# Apple1.net
KiCad netlist of a schematic drawn in EAGLE
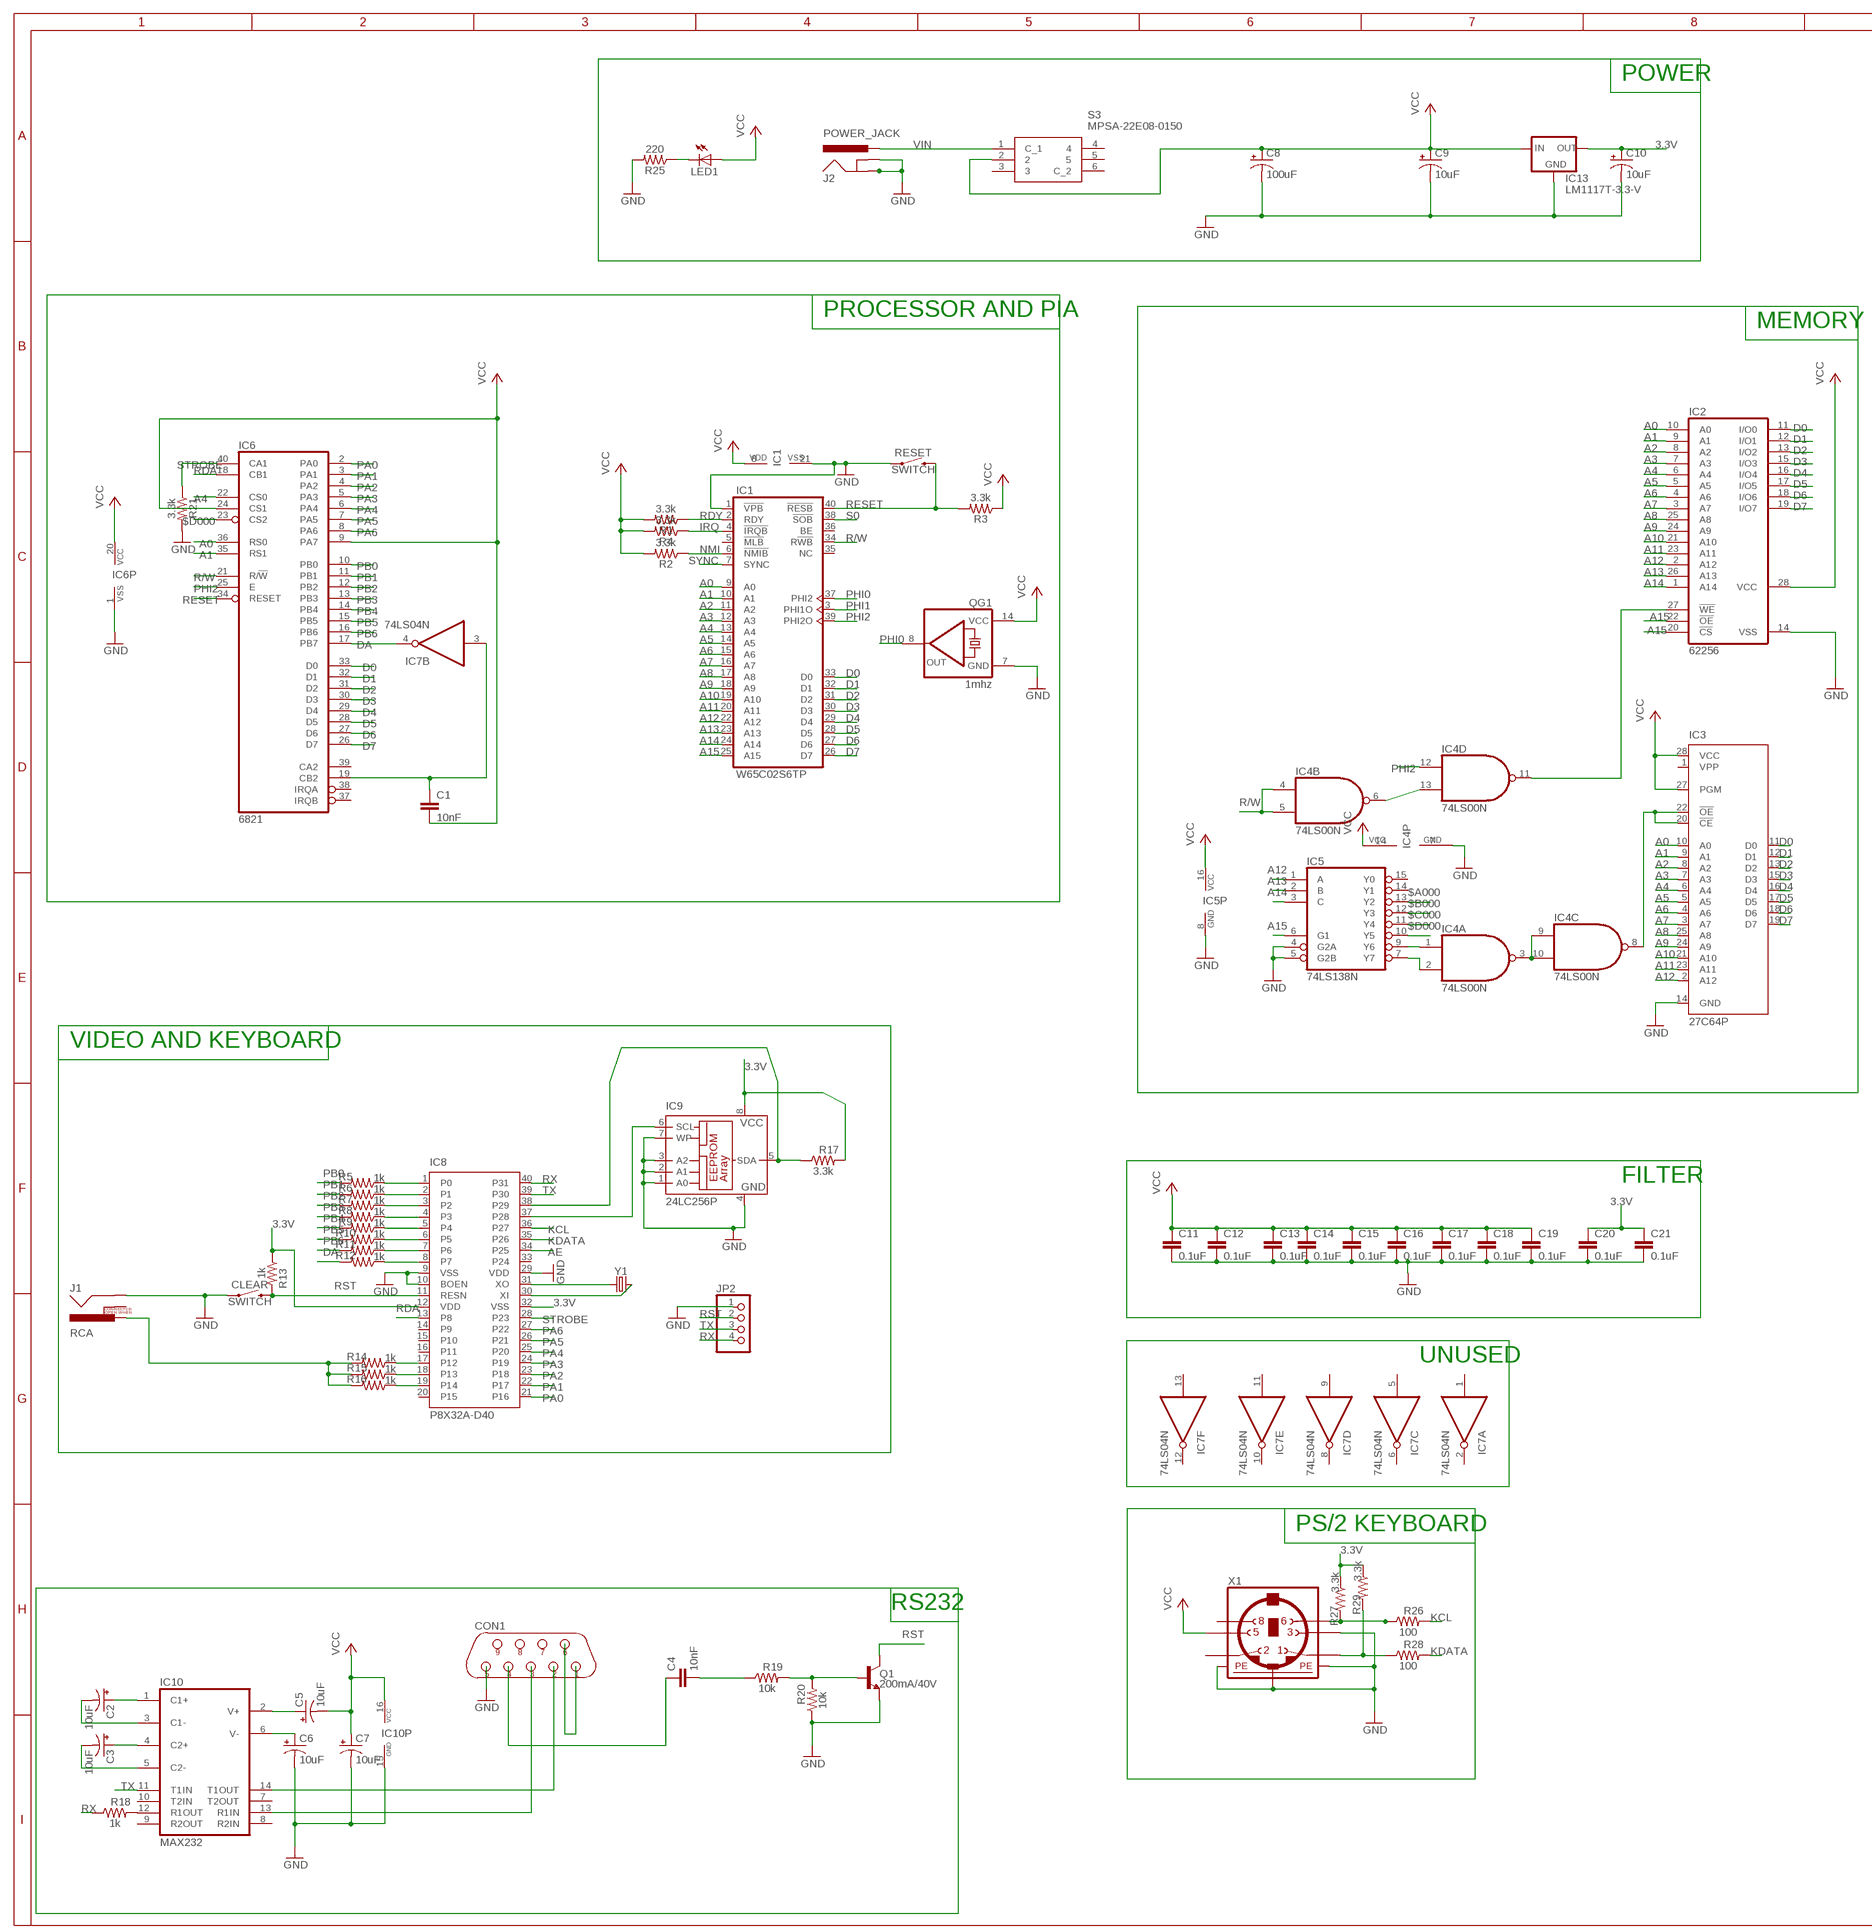
[diagram p0: schematic, sheet 1, part 1 of 2]
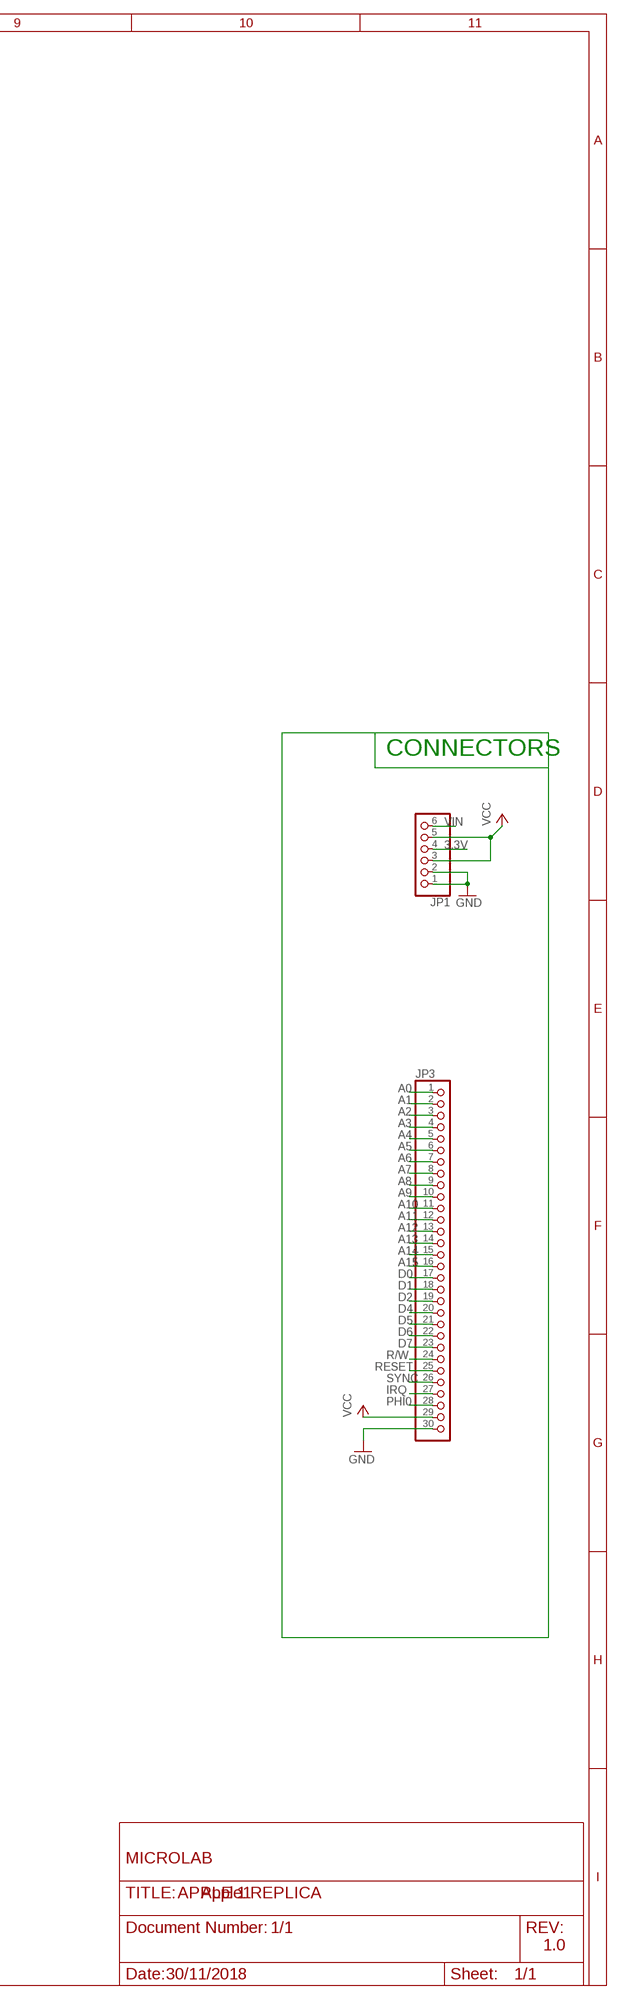
[diagram p1: schematic, sheet 1, part 2 of 2]

(export (version "E")
  (design (tool "Eeschema 10.0.6"))
  (components
    (comp (ref "C1")
      (value "10nF")
      (footprint "eagle-import:CAP-PTH-10MM")
      (libsource (lib "eagle-import") (part "10NF-PTH-10MM-10000V-1-%"))
    )
    (comp (ref "C2")
      (value "10uF")
      (footprint "eagle-import:CPOL-RADIAL-2.5MM-5MM")
      (libsource (lib "eagle-import") (part "10UF-POLAR-RADIAL-2.5MM-25V-20%"))
    )
    (comp (ref "C3")
      (value "10uF")
      (footprint "eagle-import:CPOL-RADIAL-2.5MM-5MM")
      (libsource (lib "eagle-import") (part "10UF-POLAR-RADIAL-2.5MM-25V-20%"))
    )
    (comp (ref "C4")
      (value "10nF")
      (footprint "eagle-import:CAP-PTH-10MM")
      (libsource (lib "eagle-import") (part "10NF-PTH-10MM-10000V-1-%"))
    )
    (comp (ref "C5")
      (value "10uF")
      (footprint "eagle-import:CPOL-RADIAL-2.5MM-5MM")
      (libsource (lib "eagle-import") (part "10UF-POLAR-RADIAL-2.5MM-25V-20%"))
    )
    (comp (ref "C6")
      (value "10uF")
      (footprint "eagle-import:CPOL-RADIAL-2.5MM-5MM")
      (libsource (lib "eagle-import") (part "10UF-POLAR-RADIAL-2.5MM-25V-20%"))
    )
    (comp (ref "C7")
      (value "10uF")
      (footprint "eagle-import:CPOL-RADIAL-2.5MM-5MM")
      (libsource (lib "eagle-import") (part "10UF-POLAR-RADIAL-2.5MM-25V-20%"))
    )
    (comp (ref "C8")
      (value "100uF")
      (footprint "eagle-import:CPOL-RADIAL-2.5MM-6.5MM")
      (libsource (lib "eagle-import") (part "100UF-POLAR-RADIAL-2.5MM-25V-20%"))
    )
    (comp (ref "C9")
      (value "10uF")
      (footprint "eagle-import:CPOL-RADIAL-2.5MM-5MM")
      (libsource (lib "eagle-import") (part "10UF-POLAR-RADIAL-2.5MM-25V-20%"))
    )
    (comp (ref "C10")
      (value "10uF")
      (footprint "eagle-import:CPOL-RADIAL-2.5MM-5MM")
      (libsource (lib "eagle-import") (part "10UF-POLAR-RADIAL-2.5MM-25V-20%"))
    )
    (comp (ref "C11")
      (value "0.1uF")
      (footprint "eagle-import:CAP-PTH-SMALL-KIT")
      (libsource (lib "eagle-import") (part "0.1UF-KIT-EZ-50V-20%"))
    )
    (comp (ref "C12")
      (value "0.1uF")
      (footprint "eagle-import:CAP-PTH-SMALL-KIT")
      (libsource (lib "eagle-import") (part "0.1UF-KIT-EZ-50V-20%"))
    )
    (comp (ref "C13")
      (value "0.1uF")
      (footprint "eagle-import:CAP-PTH-SMALL-KIT")
      (libsource (lib "eagle-import") (part "0.1UF-KIT-EZ-50V-20%"))
    )
    (comp (ref "C14")
      (value "0.1uF")
      (footprint "eagle-import:CAP-PTH-SMALL-KIT")
      (libsource (lib "eagle-import") (part "0.1UF-KIT-EZ-50V-20%"))
    )
    (comp (ref "C15")
      (value "0.1uF")
      (footprint "eagle-import:CAP-PTH-SMALL-KIT")
      (libsource (lib "eagle-import") (part "0.1UF-KIT-EZ-50V-20%"))
    )
    (comp (ref "C16")
      (value "0.1uF")
      (footprint "eagle-import:CAP-PTH-SMALL-KIT")
      (libsource (lib "eagle-import") (part "0.1UF-KIT-EZ-50V-20%"))
    )
    (comp (ref "C17")
      (value "0.1uF")
      (footprint "eagle-import:CAP-PTH-SMALL-KIT")
      (libsource (lib "eagle-import") (part "0.1UF-KIT-EZ-50V-20%"))
    )
    (comp (ref "C18")
      (value "0.1uF")
      (footprint "eagle-import:CAP-PTH-SMALL-KIT")
      (libsource (lib "eagle-import") (part "0.1UF-KIT-EZ-50V-20%"))
    )
    (comp (ref "C19")
      (value "0.1uF")
      (footprint "eagle-import:CAP-PTH-SMALL-KIT")
      (libsource (lib "eagle-import") (part "0.1UF-KIT-EZ-50V-20%"))
    )
    (comp (ref "C20")
      (value "0.1uF")
      (footprint "eagle-import:CAP-PTH-SMALL-KIT")
      (libsource (lib "eagle-import") (part "0.1UF-KIT-EZ-50V-20%"))
    )
    (comp (ref "C21")
      (value "0.1uF")
      (footprint "eagle-import:CAP-PTH-SMALL-KIT")
      (libsource (lib "eagle-import") (part "0.1UF-KIT-EZ-50V-20%"))
    )
    (comp (ref "CLEAR")
      (value "SWITCH")
      (footprint "eagle-import:TACTILE_SWITCH_PTH_6.0MM")
      (libsource (lib "eagle-import") (part "MOMENTARY-SWITCH-SPST-PTH-6.0MM"))
    )
    (comp (ref "CON1")
      (value "DB9F")
      (footprint "eagle-import:D-09F")
      (libsource (lib "eagle-import") (part "DB9F"))
    )
    (comp (ref "IC1")
      (value "W65C02S6TP")
      (footprint "eagle-import:DIL40")
      (libsource (lib "eagle-import") (part "W65C02SP6T"))
    )
    (comp (ref "IC2")
      (value "62256")
      (footprint "eagle-import:DIL28-6")
      (libsource (lib "eagle-import") (part "62256P"))
    )
    (comp (ref "IC3")
      (value "27C64P")
      (footprint "eagle-import:DIL28-6")
      (fields (field (name "MF") "Arrow Electronics") (field (name "MPN") "M27C64A-10F1"))
      (libsource (lib "eagle-import") (part "2764PC"))
    )
    (comp (ref "IC4")
      (value "74LS00N")
      (footprint "eagle-import:DIL14")
      (libsource (lib "eagle-import") (part "7400NLS"))
    )
    (comp (ref "IC5")
      (value "74LS138N")
      (footprint "eagle-import:DIL16")
      (libsource (lib "eagle-import") (part "74138NLS"))
    )
    (comp (ref "IC6")
      (value "6821")
      (footprint "eagle-import:DIL40")
      (fields (field (name "MF") "NTE ELECTRONICS") (field (name "MPN") "NTE6821"))
      (libsource (lib "eagle-import") (part "6821"))
    )
    (comp (ref "IC7")
      (value "74LS04N")
      (footprint "eagle-import:DIL14")
      (libsource (lib "eagle-import") (part "7404NLS"))
    )
    (comp (ref "IC8")
      (value "P8X32A-D40")
      (footprint "eagle-import:DIL40")
      (fields (field (name "MF") "Parallax Semiconductor"))
      (libsource (lib "eagle-import") (part "P8X32A-D40"))
    )
    (comp (ref "IC9")
      (value "24LC256P")
      (footprint "eagle-import:DIL8")
      (fields (field (name "MF") "MICROCHIP") (field (name "MPN") "24LC256-E/P"))
      (libsource (lib "eagle-import") (part "24PLC256"))
    )
    (comp (ref "IC10")
      (value "MAX232")
      (footprint "eagle-import:DIL16")
      (fields (field (name "MF") "MAXIM") (field (name "MPN") "MAX232ACPE+"))
      (libsource (lib "eagle-import") (part "MAX232"))
    )
    (comp (ref "IC13")
      (value "LM1117T-3.3-V")
      (footprint "eagle-import:TO220V")
      (libsource (lib "eagle-import") (part "LM1117T--V3.3"))
    )
    (comp (ref "J1")
      (value "RCA")
      (footprint "eagle-import:RCA")
      (libsource (lib "eagle-import") (part "RCA"))
    )
    (comp (ref "J2")
      (value "POWER_JACK")
      (footprint "eagle-import:POWER_JACK_PTH")
      (libsource (lib "eagle-import") (part "POWER_JACK"))
    )
    (comp (ref "JP1")
      (value "PINHD-1X6B")
      (footprint "eagle-import:1X06-BIG")
      (libsource (lib "eagle-import") (part "PINHD-1X6B"))
    )
    (comp (ref "JP2")
      (value "PINHD-1X4")
      (footprint "eagle-import:1X04")
      (libsource (lib "eagle-import") (part "PINHD-1X4"))
    )
    (comp (ref "JP3")
      (value "PINHD-1X30")
      (footprint "eagle-import:1X30")
      (libsource (lib "eagle-import") (part "PINHD-1X30"))
    )
    (comp (ref "LED1")
      (value "LED5MM")
      (footprint "eagle-import:LED5MM")
      (libsource (lib "eagle-import") (part "LED5MM"))
    )
    (comp (ref "Q1")
      (value "200mA/40V")
      (footprint "eagle-import:TO-92")
      (libsource (lib "eagle-import") (part "TRANS_NPN-2N3904"))
    )
    (comp (ref "QG1")
      (value "1mhz")
      (footprint "eagle-import:DIL14S")
      (libsource (lib "eagle-import") (part "QG5860"))
    )
    (comp (ref "R1")
      (value "3.3k")
      (footprint "eagle-import:AXIAL-0.3")
      (libsource (lib "eagle-import") (part "10KOHM-HORIZ-1/4W-5%"))
    )
    (comp (ref "R2")
      (value "3.3k")
      (footprint "eagle-import:AXIAL-0.3")
      (libsource (lib "eagle-import") (part "10KOHM-HORIZ-1/4W-5%"))
    )
    (comp (ref "R3")
      (value "3.3k")
      (footprint "eagle-import:AXIAL-0.3")
      (libsource (lib "eagle-import") (part "10KOHM-HORIZ-1/4W-5%"))
    )
    (comp (ref "R4")
      (value "3.3k")
      (footprint "eagle-import:AXIAL-0.3")
      (libsource (lib "eagle-import") (part "10KOHM-HORIZ-1/4W-5%"))
    )
    (comp (ref "R5")
      (value "1k")
      (footprint "eagle-import:AXIAL-0.3")
      (libsource (lib "eagle-import") (part "10KOHM-HORIZ-1/4W-5%"))
    )
    (comp (ref "R6")
      (value "1k")
      (footprint "eagle-import:AXIAL-0.3")
      (libsource (lib "eagle-import") (part "10KOHM-HORIZ-1/4W-5%"))
    )
    (comp (ref "R7")
      (value "1k")
      (footprint "eagle-import:AXIAL-0.3")
      (libsource (lib "eagle-import") (part "10KOHM-HORIZ-1/4W-5%"))
    )
    (comp (ref "R8")
      (value "1k")
      (footprint "eagle-import:AXIAL-0.3")
      (libsource (lib "eagle-import") (part "10KOHM-HORIZ-1/4W-5%"))
    )
    (comp (ref "R9")
      (value "1k")
      (footprint "eagle-import:AXIAL-0.3")
      (libsource (lib "eagle-import") (part "10KOHM-HORIZ-1/4W-5%"))
    )
    (comp (ref "R10")
      (value "1k")
      (footprint "eagle-import:AXIAL-0.3")
      (libsource (lib "eagle-import") (part "10KOHM-HORIZ-1/4W-5%"))
    )
    (comp (ref "R11")
      (value "1k")
      (footprint "eagle-import:AXIAL-0.3")
      (libsource (lib "eagle-import") (part "10KOHM-HORIZ-1/4W-5%"))
    )
    (comp (ref "R12")
      (value "1k")
      (footprint "eagle-import:AXIAL-0.3")
      (libsource (lib "eagle-import") (part "10KOHM-HORIZ-1/4W-5%"))
    )
    (comp (ref "R13")
      (value "1k")
      (footprint "eagle-import:AXIAL-0.3")
      (libsource (lib "eagle-import") (part "10KOHM-HORIZ-1/4W-5%"))
    )
    (comp (ref "R14")
      (value "1k")
      (footprint "eagle-import:AXIAL-0.3")
      (libsource (lib "eagle-import") (part "10KOHM-HORIZ-1/4W-5%"))
    )
    (comp (ref "R15")
      (value "1k")
      (footprint "eagle-import:AXIAL-0.3")
      (libsource (lib "eagle-import") (part "10KOHM-HORIZ-1/4W-5%"))
    )
    (comp (ref "R16")
      (value "1k")
      (footprint "eagle-import:AXIAL-0.3")
      (libsource (lib "eagle-import") (part "10KOHM-HORIZ-1/4W-5%"))
    )
    (comp (ref "R17")
      (value "3.3k")
      (footprint "eagle-import:AXIAL-0.3")
      (libsource (lib "eagle-import") (part "10KOHM-HORIZ-1/4W-5%"))
    )
    (comp (ref "R18")
      (value "1k")
      (footprint "eagle-import:AXIAL-0.3")
      (libsource (lib "eagle-import") (part "10KOHM-HORIZ-1/4W-5%"))
    )
    (comp (ref "R19")
      (value "10k")
      (footprint "eagle-import:AXIAL-0.3")
      (libsource (lib "eagle-import") (part "10KOHM-HORIZ-1/4W-5%"))
    )
    (comp (ref "R20")
      (value "10k")
      (footprint "eagle-import:AXIAL-0.3")
      (libsource (lib "eagle-import") (part "10KOHM-HORIZ-1/4W-5%"))
    )
    (comp (ref "R21")
      (value "3.3k")
      (footprint "eagle-import:AXIAL-0.3")
      (libsource (lib "eagle-import") (part "10KOHM-HORIZ-1/4W-5%"))
    )
    (comp (ref "R25")
      (value "220")
      (footprint "eagle-import:AXIAL-0.3")
      (libsource (lib "eagle-import") (part "10KOHM-HORIZ-1/4W-5%"))
    )
    (comp (ref "R26")
      (value "100")
      (footprint "eagle-import:AXIAL-0.3")
      (libsource (lib "eagle-import") (part "10KOHM-HORIZ-1/4W-5%"))
    )
    (comp (ref "R27")
      (value "3.3k")
      (footprint "eagle-import:AXIAL-0.3")
      (libsource (lib "eagle-import") (part "10KOHM-HORIZ-1/4W-5%"))
    )
    (comp (ref "R28")
      (value "100")
      (footprint "eagle-import:AXIAL-0.3")
      (libsource (lib "eagle-import") (part "10KOHM-HORIZ-1/4W-5%"))
    )
    (comp (ref "R29")
      (value "3.3k")
      (footprint "eagle-import:AXIAL-0.3")
      (libsource (lib "eagle-import") (part "10KOHM-HORIZ-1/4W-5%"))
    )
    (comp (ref "RESET")
      (value "SWITCH")
      (footprint "eagle-import:TACTILE_SWITCH_PTH_6.0MM")
      (libsource (lib "eagle-import") (part "MOMENTARY-SWITCH-SPST-PTH-6.0MM"))
    )
    (comp (ref "S3")
      (value "MPSA-22E08-0150")
      (footprint "eagle-import:MPSA22E080150")
      (fields (field (name "RS_PART_NUMBER") "9138895"))
      (libsource (lib "eagle-import") (part "MPSA-22E08-0150"))
    )
    (comp (ref "X1")
      (value "MINI_DIN_6")
      (footprint "eagle-import:M_DIN6")
      (libsource (lib "eagle-import") (part "MINI_DIN_6"))
    )
    (comp (ref "Y1")
      (value "CRYSTALPTH-HC49UV")
      (footprint "eagle-import:HC49U")
      (libsource (lib "eagle-import") (part "CRYSTALPTH-HC49UV"))
    )
  )
  (nets
    (net (code "1") (name "/$A000") (class "Default")
      (node (ref "IC5") (pin "13") (pinfunction "Y2_13") (pintype "output"))
    )
    (net (code "2") (name "/$B000") (class "Default")
      (node (ref "IC5") (pin "12") (pinfunction "Y3_12") (pintype "output"))
    )
    (net (code "3") (name "/$C000") (class "Default")
      (node (ref "IC5") (pin "11") (pinfunction "Y4_11") (pintype "output"))
    )
    (net (code "4") (name "/$D000") (class "Default")
      (node (ref "IC5") (pin "10") (pinfunction "Y5_10") (pintype "output"))
      (node (ref "IC6") (pin "23") (pinfunction "CS2_23") (pintype "input"))
    )
    (net (code "5") (name "/3.3V") (class "Default")
      (node (ref "C10") (pin "1") (pinfunction "+_1") (pintype "passive"))
      (node (ref "C20") (pin "1") (pinfunction "1_1") (pintype "passive"))
      (node (ref "C21") (pin "1") (pinfunction "1_1") (pintype "passive"))
      (node (ref "IC13") (pin "2") (pinfunction "OUT_2") (pintype "passive"))
      (node (ref "IC8") (pin "12") (pinfunction "VDD_12") (pintype "power_in"))
      (node (ref "IC8") (pin "32") (pinfunction "VSS_32") (pintype "power_in"))
      (node (ref "IC9") (pin "8") (pinfunction "VCC_8") (pintype "power_in"))
      (node (ref "JP1") (pin "4") (pinfunction "4_4") (pintype "passive"))
      (node (ref "R13") (pin "P$1") (pinfunction "1_P$1") (pintype "passive"))
      (node (ref "R17") (pin "P$2") (pinfunction "2_P$2") (pintype "passive"))
      (node (ref "R27") (pin "P$1") (pinfunction "1_P$1") (pintype "passive"))
      (node (ref "R29") (pin "P$1") (pinfunction "1_P$1") (pintype "passive"))
    )
    (net (code "6") (name "/A0") (class "Default")
      (node (ref "IC1") (pin "9") (pinfunction "A0_9") (pintype "output"))
      (node (ref "IC2") (pin "10") (pinfunction "A0_10") (pintype "input"))
      (node (ref "IC3") (pin "10") (pinfunction "A0_10") (pintype "input"))
      (node (ref "IC6") (pin "36") (pinfunction "RS0_36") (pintype "input"))
      (node (ref "JP3") (pin "1") (pinfunction "1_1") (pintype "passive"))
    )
    (net (code "7") (name "/A1") (class "Default")
      (node (ref "IC1") (pin "10") (pinfunction "A1_10") (pintype "output"))
      (node (ref "IC2") (pin "9") (pinfunction "A1_9") (pintype "input"))
      (node (ref "IC3") (pin "9") (pinfunction "A1_9") (pintype "input"))
      (node (ref "IC6") (pin "35") (pinfunction "RS1_35") (pintype "input"))
      (node (ref "JP3") (pin "2") (pinfunction "2_2") (pintype "passive"))
    )
    (net (code "8") (name "/A2") (class "Default")
      (node (ref "IC1") (pin "11") (pinfunction "A2_11") (pintype "output"))
      (node (ref "IC2") (pin "8") (pinfunction "A2_8") (pintype "input"))
      (node (ref "IC3") (pin "8") (pinfunction "A2_8") (pintype "input"))
      (node (ref "JP3") (pin "3") (pinfunction "3_3") (pintype "passive"))
    )
    (net (code "9") (name "/A3") (class "Default")
      (node (ref "IC1") (pin "12") (pinfunction "A3_12") (pintype "output"))
      (node (ref "IC2") (pin "7") (pinfunction "A3_7") (pintype "input"))
      (node (ref "IC3") (pin "7") (pinfunction "A3_7") (pintype "input"))
      (node (ref "JP3") (pin "4") (pinfunction "4_4") (pintype "passive"))
    )
    (net (code "10") (name "/A4") (class "Default")
      (node (ref "IC1") (pin "13") (pinfunction "A4_13") (pintype "output"))
      (node (ref "IC2") (pin "6") (pinfunction "A4_6") (pintype "input"))
      (node (ref "IC3") (pin "6") (pinfunction "A4_6") (pintype "input"))
      (node (ref "IC6") (pin "22") (pinfunction "CS0_22") (pintype "input"))
      (node (ref "JP3") (pin "5") (pinfunction "5_5") (pintype "passive"))
    )
    (net (code "11") (name "/A5") (class "Default")
      (node (ref "IC1") (pin "14") (pinfunction "A5_14") (pintype "output"))
      (node (ref "IC2") (pin "5") (pinfunction "A5_5") (pintype "input"))
      (node (ref "IC3") (pin "5") (pinfunction "A5_5") (pintype "input"))
      (node (ref "JP3") (pin "6") (pinfunction "6_6") (pintype "passive"))
    )
    (net (code "12") (name "/A6") (class "Default")
      (node (ref "IC1") (pin "15") (pinfunction "A6_15") (pintype "output"))
      (node (ref "IC2") (pin "4") (pinfunction "A6_4") (pintype "input"))
      (node (ref "IC3") (pin "4") (pinfunction "A6_4") (pintype "input"))
      (node (ref "JP3") (pin "7") (pinfunction "7_7") (pintype "passive"))
    )
    (net (code "13") (name "/A7") (class "Default")
      (node (ref "IC1") (pin "16") (pinfunction "A7_16") (pintype "output"))
      (node (ref "IC2") (pin "3") (pinfunction "A7_3") (pintype "input"))
      (node (ref "IC3") (pin "3") (pinfunction "A7_3") (pintype "input"))
      (node (ref "JP3") (pin "8") (pinfunction "8_8") (pintype "passive"))
    )
    (net (code "14") (name "/A8") (class "Default")
      (node (ref "IC1") (pin "17") (pinfunction "A8_17") (pintype "output"))
      (node (ref "IC2") (pin "25") (pinfunction "A8_25") (pintype "input"))
      (node (ref "IC3") (pin "25") (pinfunction "A8_25") (pintype "input"))
      (node (ref "JP3") (pin "9") (pinfunction "9_9") (pintype "passive"))
    )
    (net (code "15") (name "/A9") (class "Default")
      (node (ref "IC1") (pin "18") (pinfunction "A9_18") (pintype "output"))
      (node (ref "IC2") (pin "24") (pinfunction "A9_24") (pintype "input"))
      (node (ref "IC3") (pin "24") (pinfunction "A9_24") (pintype "input"))
      (node (ref "JP3") (pin "10") (pinfunction "10_10") (pintype "passive"))
    )
    (net (code "16") (name "/A10") (class "Default")
      (node (ref "IC1") (pin "19") (pinfunction "A10_19") (pintype "output"))
      (node (ref "IC2") (pin "21") (pinfunction "A10_21") (pintype "input"))
      (node (ref "IC3") (pin "21") (pinfunction "A10_21") (pintype "input"))
      (node (ref "JP3") (pin "11") (pinfunction "11_11") (pintype "passive"))
    )
    (net (code "17") (name "/A11") (class "Default")
      (node (ref "IC1") (pin "20") (pinfunction "A11_20") (pintype "output"))
      (node (ref "IC2") (pin "23") (pinfunction "A11_23") (pintype "input"))
      (node (ref "IC3") (pin "23") (pinfunction "A11_23") (pintype "input"))
      (node (ref "JP3") (pin "12") (pinfunction "12_12") (pintype "passive"))
    )
    (net (code "18") (name "/A12") (class "Default")
      (node (ref "IC1") (pin "22") (pinfunction "A12_22") (pintype "output"))
      (node (ref "IC2") (pin "2") (pinfunction "A12_2") (pintype "input"))
      (node (ref "IC3") (pin "2") (pinfunction "A12_2") (pintype "input"))
      (node (ref "IC5") (pin "1") (pinfunction "A_1") (pintype "input"))
      (node (ref "JP3") (pin "13") (pinfunction "13_13") (pintype "passive"))
    )
    (net (code "19") (name "/A13") (class "Default")
      (node (ref "IC1") (pin "23") (pinfunction "A13_23") (pintype "output"))
      (node (ref "IC2") (pin "26") (pinfunction "A13_26") (pintype "input"))
      (node (ref "IC5") (pin "2") (pinfunction "B_2") (pintype "input"))
      (node (ref "JP3") (pin "14") (pinfunction "14_14") (pintype "passive"))
    )
    (net (code "20") (name "/A14") (class "Default")
      (node (ref "IC1") (pin "24") (pinfunction "A14_24") (pintype "output"))
      (node (ref "IC2") (pin "1") (pinfunction "A14_1") (pintype "input"))
      (node (ref "IC5") (pin "3") (pinfunction "C_3") (pintype "input"))
      (node (ref "JP3") (pin "15") (pinfunction "15_15") (pintype "passive"))
    )
    (net (code "21") (name "/A15") (class "Default")
      (node (ref "IC1") (pin "25") (pinfunction "A15_25") (pintype "output"))
      (node (ref "IC2") (pin "20") (pinfunction "~{CS}_20") (pintype "input"))
      (node (ref "IC2") (pin "22") (pinfunction "~{OE}_22") (pintype "input"))
      (node (ref "IC5") (pin "6") (pinfunction "G1_6") (pintype "input"))
      (node (ref "JP3") (pin "16") (pinfunction "16_16") (pintype "passive"))
    )
    (net (code "22") (name "/AE") (class "Default")
      (node (ref "IC8") (pin "34") (pinfunction "P25_34") (pintype "bidirectional"))
    )
    (net (code "23") (name "/D0") (class "Default")
      (node (ref "IC1") (pin "33") (pinfunction "D0_33") (pintype "bidirectional"))
      (node (ref "IC2") (pin "11") (pinfunction "I/O0_11") (pintype "bidirectional"))
      (node (ref "IC3") (pin "11") (pinfunction "D0_11") (pintype "tri_state"))
      (node (ref "IC6") (pin "33") (pinfunction "D0_33") (pintype "bidirectional"))
      (node (ref "JP3") (pin "17") (pinfunction "17_17") (pintype "passive"))
    )
    (net (code "24") (name "/D1") (class "Default")
      (node (ref "IC1") (pin "32") (pinfunction "D1_32") (pintype "bidirectional"))
      (node (ref "IC2") (pin "12") (pinfunction "I/O1_12") (pintype "bidirectional"))
      (node (ref "IC3") (pin "12") (pinfunction "D1_12") (pintype "tri_state"))
      (node (ref "IC6") (pin "32") (pinfunction "D1_32") (pintype "bidirectional"))
      (node (ref "JP3") (pin "18") (pinfunction "18_18") (pintype "passive"))
    )
    (net (code "25") (name "/D2") (class "Default")
      (node (ref "IC1") (pin "31") (pinfunction "D2_31") (pintype "bidirectional"))
      (node (ref "IC2") (pin "13") (pinfunction "I/O2_13") (pintype "bidirectional"))
      (node (ref "IC3") (pin "13") (pinfunction "D2_13") (pintype "tri_state"))
      (node (ref "IC6") (pin "31") (pinfunction "D2_31") (pintype "bidirectional"))
      (node (ref "JP3") (pin "19") (pinfunction "19_19") (pintype "passive"))
    )
    (net (code "26") (name "/D3") (class "Default")
      (node (ref "IC1") (pin "30") (pinfunction "D3_30") (pintype "bidirectional"))
      (node (ref "IC2") (pin "15") (pinfunction "I/O3_15") (pintype "bidirectional"))
      (node (ref "IC3") (pin "15") (pinfunction "D3_15") (pintype "tri_state"))
      (node (ref "IC6") (pin "30") (pinfunction "D3_30") (pintype "bidirectional"))
    )
    (net (code "27") (name "/D4") (class "Default")
      (node (ref "IC1") (pin "29") (pinfunction "D4_29") (pintype "bidirectional"))
      (node (ref "IC2") (pin "16") (pinfunction "I/O4_16") (pintype "bidirectional"))
      (node (ref "IC3") (pin "16") (pinfunction "D4_16") (pintype "tri_state"))
      (node (ref "IC6") (pin "29") (pinfunction "D4_29") (pintype "bidirectional"))
      (node (ref "JP3") (pin "20") (pinfunction "20_20") (pintype "passive"))
    )
    (net (code "28") (name "/D5") (class "Default")
      (node (ref "IC1") (pin "28") (pinfunction "D5_28") (pintype "bidirectional"))
      (node (ref "IC2") (pin "17") (pinfunction "I/O5_17") (pintype "bidirectional"))
      (node (ref "IC3") (pin "17") (pinfunction "D5_17") (pintype "tri_state"))
      (node (ref "IC6") (pin "28") (pinfunction "D5_28") (pintype "bidirectional"))
      (node (ref "JP3") (pin "21") (pinfunction "21_21") (pintype "passive"))
    )
    (net (code "29") (name "/D6") (class "Default")
      (node (ref "IC1") (pin "27") (pinfunction "D6_27") (pintype "bidirectional"))
      (node (ref "IC2") (pin "18") (pinfunction "I/O6_18") (pintype "bidirectional"))
      (node (ref "IC3") (pin "18") (pinfunction "D6_18") (pintype "tri_state"))
      (node (ref "IC6") (pin "27") (pinfunction "D6_27") (pintype "bidirectional"))
      (node (ref "JP3") (pin "22") (pinfunction "22_22") (pintype "passive"))
    )
    (net (code "30") (name "/D7") (class "Default")
      (node (ref "IC1") (pin "26") (pinfunction "D7_26") (pintype "bidirectional"))
      (node (ref "IC2") (pin "19") (pinfunction "I/O7_19") (pintype "bidirectional"))
      (node (ref "IC3") (pin "19") (pinfunction "D7_19") (pintype "tri_state"))
      (node (ref "IC6") (pin "26") (pinfunction "D7_26") (pintype "bidirectional"))
      (node (ref "JP3") (pin "23") (pinfunction "23_23") (pintype "passive"))
    )
    (net (code "31") (name "/DA") (class "Default")
      (node (ref "IC6") (pin "17") (pinfunction "PB7_17") (pintype "bidirectional"))
      (node (ref "IC7") (pin "4") (pinfunction "O_4") (pintype "output"))
      (node (ref "R12") (pin "P$2") (pinfunction "2_P$2") (pintype "passive"))
    )
    (net (code "32") (name "/IRQ") (class "Default")
      (node (ref "IC1") (pin "4") (pinfunction "~{IRQB}_4") (pintype "input"))
      (node (ref "JP3") (pin "27") (pinfunction "27_27") (pintype "passive"))
      (node (ref "R4") (pin "P$1") (pinfunction "1_P$1") (pintype "passive"))
    )
    (net (code "33") (name "/KCL") (class "Default")
      (node (ref "IC8") (pin "36") (pinfunction "P27_36") (pintype "bidirectional"))
      (node (ref "R26") (pin "P$2") (pinfunction "2_P$2") (pintype "passive"))
    )
    (net (code "34") (name "/KDATA") (class "Default")
      (node (ref "IC8") (pin "35") (pinfunction "P26_35") (pintype "bidirectional"))
      (node (ref "R28") (pin "P$2") (pinfunction "2_P$2") (pintype "passive"))
    )
    (net (code "35") (name "/NMI") (class "Default")
      (node (ref "IC1") (pin "6") (pinfunction "~{NMIB}_6") (pintype "input"))
      (node (ref "R2") (pin "P$1") (pinfunction "1_P$1") (pintype "passive"))
    )
    (net (code "36") (name "/PA0") (class "Default")
      (node (ref "IC6") (pin "2") (pinfunction "PA0_2") (pintype "bidirectional"))
      (node (ref "IC8") (pin "21") (pinfunction "P16_21") (pintype "bidirectional"))
    )
    (net (code "37") (name "/PA1") (class "Default")
      (node (ref "IC6") (pin "3") (pinfunction "PA1_3") (pintype "bidirectional"))
      (node (ref "IC8") (pin "22") (pinfunction "P17_22") (pintype "bidirectional"))
    )
    (net (code "38") (name "/PA2") (class "Default")
      (node (ref "IC6") (pin "4") (pinfunction "PA2_4") (pintype "bidirectional"))
      (node (ref "IC8") (pin "23") (pinfunction "P18_23") (pintype "bidirectional"))
    )
    (net (code "39") (name "/PA3") (class "Default")
      (node (ref "IC6") (pin "5") (pinfunction "PA3_5") (pintype "bidirectional"))
      (node (ref "IC8") (pin "24") (pinfunction "P19_24") (pintype "bidirectional"))
    )
    (net (code "40") (name "/PA4") (class "Default")
      (node (ref "IC6") (pin "6") (pinfunction "PA4_6") (pintype "bidirectional"))
      (node (ref "IC8") (pin "25") (pinfunction "P20_25") (pintype "bidirectional"))
    )
    (net (code "41") (name "/PA5") (class "Default")
      (node (ref "IC6") (pin "7") (pinfunction "PA5_7") (pintype "bidirectional"))
      (node (ref "IC8") (pin "26") (pinfunction "P21_26") (pintype "bidirectional"))
    )
    (net (code "42") (name "/PA6") (class "Default")
      (node (ref "IC6") (pin "8") (pinfunction "PA6_8") (pintype "bidirectional"))
      (node (ref "IC8") (pin "27") (pinfunction "P22_27") (pintype "bidirectional"))
    )
    (net (code "43") (name "/PB0") (class "Default")
      (node (ref "IC6") (pin "10") (pinfunction "PB0_10") (pintype "bidirectional"))
      (node (ref "R5") (pin "P$2") (pinfunction "2_P$2") (pintype "passive"))
    )
    (net (code "44") (name "/PB1") (class "Default")
      (node (ref "IC6") (pin "11") (pinfunction "PB1_11") (pintype "bidirectional"))
      (node (ref "R6") (pin "P$2") (pinfunction "2_P$2") (pintype "passive"))
    )
    (net (code "45") (name "/PB2") (class "Default")
      (node (ref "IC6") (pin "12") (pinfunction "PB2_12") (pintype "bidirectional"))
      (node (ref "R7") (pin "P$2") (pinfunction "2_P$2") (pintype "passive"))
    )
    (net (code "46") (name "/PB3") (class "Default")
      (node (ref "IC6") (pin "13") (pinfunction "PB3_13") (pintype "bidirectional"))
      (node (ref "R8") (pin "P$2") (pinfunction "2_P$2") (pintype "passive"))
    )
    (net (code "47") (name "/PB4") (class "Default")
      (node (ref "IC6") (pin "14") (pinfunction "PB4_14") (pintype "bidirectional"))
      (node (ref "R9") (pin "P$2") (pinfunction "2_P$2") (pintype "passive"))
    )
    (net (code "48") (name "/PB5") (class "Default")
      (node (ref "IC6") (pin "15") (pinfunction "PB5_15") (pintype "bidirectional"))
      (node (ref "R10") (pin "P$2") (pinfunction "2_P$2") (pintype "passive"))
    )
    (net (code "49") (name "/PB6") (class "Default")
      (node (ref "IC6") (pin "16") (pinfunction "PB6_16") (pintype "bidirectional"))
      (node (ref "R11") (pin "P$2") (pinfunction "2_P$2") (pintype "passive"))
    )
    (net (code "50") (name "/PHI0") (class "Default")
      (node (ref "IC1") (pin "37") (pinfunction "PHI2_37") (pintype "input"))
      (node (ref "JP3") (pin "28") (pinfunction "28_28") (pintype "passive"))
      (node (ref "QG1") (pin "8") (pinfunction "OUT_8") (pintype "output"))
    )
    (net (code "51") (name "/PHI1") (class "Default")
      (node (ref "IC1") (pin "3") (pinfunction "PHI1O_3") (pintype "output"))
    )
    (net (code "52") (name "/PHI2") (class "Default")
      (node (ref "IC1") (pin "39") (pinfunction "PHI2O_39") (pintype "output"))
      (node (ref "IC4") (pin "12") (pinfunction "I0_12") (pintype "input"))
      (node (ref "IC6") (pin "25") (pinfunction "E_25") (pintype "input"))
    )
    (net (code "53") (name "/RDA") (class "Default")
      (node (ref "IC6") (pin "18") (pinfunction "CB1_18") (pintype "input"))
      (node (ref "IC8") (pin "13") (pinfunction "P8_13") (pintype "bidirectional"))
    )
    (net (code "54") (name "/RDY") (class "Default")
      (node (ref "IC1") (pin "2") (pinfunction "RDY_2") (pintype "input"))
      (node (ref "R1") (pin "P$1") (pinfunction "1_P$1") (pintype "passive"))
    )
    (net (code "55") (name "/RESET") (class "Default")
      (node (ref "IC1") (pin "40") (pinfunction "~{RESB}_40") (pintype "input"))
      (node (ref "IC6") (pin "34") (pinfunction "RESET_34") (pintype "input"))
      (node (ref "JP3") (pin "25") (pinfunction "25_25") (pintype "passive"))
      (node (ref "R3") (pin "P$2") (pinfunction "2_P$2") (pintype "passive"))
      (node (ref "RESET") (pin "3") (pinfunction "2_3") (pintype "passive"))
    )
    (net (code "56") (name "/RST") (class "Default")
      (node (ref "CLEAR") (pin "3") (pinfunction "2_3") (pintype "passive"))
      (node (ref "IC8") (pin "11") (pinfunction "RESN_11") (pintype "bidirectional"))
      (node (ref "JP2") (pin "2") (pinfunction "2_2") (pintype "passive"))
      (node (ref "Q1") (pin "3") (pinfunction "C_3") (pintype "passive"))
      (node (ref "R13") (pin "P$2") (pinfunction "2_P$2") (pintype "passive"))
    )
    (net (code "57") (name "/RX") (class "Default")
      (node (ref "IC8") (pin "40") (pinfunction "P31_40") (pintype "bidirectional"))
      (node (ref "JP2") (pin "4") (pinfunction "4_4") (pintype "passive"))
      (node (ref "R18") (pin "P$1") (pinfunction "1_P$1") (pintype "passive"))
    )
    (net (code "58") (name "/R{slash}W") (class "Default")
      (node (ref "IC1") (pin "34") (pinfunction "R~{WB}_34") (pintype "output"))
      (node (ref "IC4") (pin "4") (pinfunction "I0_4") (pintype "input"))
      (node (ref "IC4") (pin "5") (pinfunction "I1_5") (pintype "input"))
      (node (ref "IC6") (pin "21") (pinfunction "R/~{W}_21") (pintype "input"))
      (node (ref "JP3") (pin "24") (pinfunction "24_24") (pintype "passive"))
    )
    (net (code "59") (name "/S0") (class "Default")
      (node (ref "IC1") (pin "38") (pinfunction "~{SOB}_38") (pintype "input"))
    )
    (net (code "60") (name "/STROBE") (class "Default")
      (node (ref "IC6") (pin "40") (pinfunction "CA1_40") (pintype "input"))
      (node (ref "IC8") (pin "28") (pinfunction "P23_28") (pintype "bidirectional"))
      (node (ref "R21") (pin "P$1") (pinfunction "1_P$1") (pintype "passive"))
    )
    (net (code "61") (name "/SYNC") (class "Default")
      (node (ref "IC1") (pin "7") (pinfunction "SYNC_7") (pintype "output"))
      (node (ref "JP3") (pin "26") (pinfunction "26_26") (pintype "passive"))
    )
    (net (code "62") (name "/TX") (class "Default")
      (node (ref "IC10") (pin "11") (pinfunction "T1IN_11") (pintype "input"))
      (node (ref "IC8") (pin "39") (pinfunction "P30_39") (pintype "bidirectional"))
      (node (ref "JP2") (pin "3") (pinfunction "3_3") (pintype "passive"))
    )
    (net (code "63") (name "/VIN") (class "Default")
      (node (ref "J2") (pin "PWR") (pinfunction "PWR_PWR") (pintype "bidirectional"))
      (node (ref "JP1") (pin "6") (pinfunction "6_6") (pintype "passive"))
      (node (ref "S3") (pin "1") (pinfunction "C_1_1") (pintype "bidirectional"))
    )
    (net (code "64") (name "GND") (class "Default")
      (node (ref "C10") (pin "2") (pinfunction "-_2") (pintype "passive"))
      (node (ref "C11") (pin "2") (pinfunction "2_2") (pintype "passive"))
      (node (ref "C12") (pin "2") (pinfunction "2_2") (pintype "passive"))
      (node (ref "C13") (pin "2") (pinfunction "2_2") (pintype "passive"))
      (node (ref "C14") (pin "2") (pinfunction "2_2") (pintype "passive"))
      (node (ref "C15") (pin "2") (pinfunction "2_2") (pintype "passive"))
      (node (ref "C16") (pin "2") (pinfunction "2_2") (pintype "passive"))
      (node (ref "C17") (pin "2") (pinfunction "2_2") (pintype "passive"))
      (node (ref "C18") (pin "2") (pinfunction "2_2") (pintype "passive"))
      (node (ref "C19") (pin "2") (pinfunction "2_2") (pintype "passive"))
      (node (ref "C20") (pin "2") (pinfunction "2_2") (pintype "passive"))
      (node (ref "C21") (pin "2") (pinfunction "2_2") (pintype "passive"))
      (node (ref "C6") (pin "2") (pinfunction "-_2") (pintype "passive"))
      (node (ref "C7") (pin "2") (pinfunction "-_2") (pintype "passive"))
      (node (ref "C8") (pin "2") (pinfunction "-_2") (pintype "passive"))
      (node (ref "C9") (pin "2") (pinfunction "-_2") (pintype "passive"))
      (node (ref "CLEAR") (pin "1") (pinfunction "1_1") (pintype "passive"))
      (node (ref "CON1") (pin "5") (pinfunction "5_5") (pintype "passive"))
      (node (ref "IC1") (pin "1") (pinfunction "~{VPB}_1") (pintype "output"))
      (node (ref "IC1") (pin "21") (pinfunction "VSS_21") (pintype "power_in"))
      (node (ref "IC10") (pin "15") (pinfunction "GND_15") (pintype "power_in"))
      (node (ref "IC13") (pin "1") (pinfunction "GND_1") (pintype "input"))
      (node (ref "IC2") (pin "14") (pinfunction "VSS_14") (pintype "power_in"))
      (node (ref "IC3") (pin "14") (pinfunction "GND_14") (pintype "power_in"))
      (node (ref "IC4") (pin "7") (pinfunction "GND_7") (pintype "power_in"))
      (node (ref "IC5") (pin "4") (pinfunction "G2A_4") (pintype "input"))
      (node (ref "IC5") (pin "5") (pinfunction "G2B_5") (pintype "input"))
      (node (ref "IC5") (pin "8") (pinfunction "GND_8") (pintype "power_in"))
      (node (ref "IC6") (pin "1") (pinfunction "VSS_1") (pintype "power_in"))
      (node (ref "IC8") (pin "10") (pinfunction "BOEN_10") (pintype "input"))
      (node (ref "IC8") (pin "29") (pinfunction "VDD_29") (pintype "power_in"))
      (node (ref "IC8") (pin "9") (pinfunction "VSS_9") (pintype "power_in"))
      (node (ref "IC9") (pin "1") (pinfunction "A0_1") (pintype "input"))
      (node (ref "IC9") (pin "2") (pinfunction "A1_2") (pintype "input"))
      (node (ref "IC9") (pin "3") (pinfunction "A2_3") (pintype "input"))
      (node (ref "IC9") (pin "4") (pinfunction "GND_4") (pintype "power_in"))
      (node (ref "IC9") (pin "7") (pinfunction "WP_7") (pintype "input"))
      (node (ref "J1") (pin "SHELL") (pinfunction "SHELL_SHELL") (pintype "bidirectional"))
      (node (ref "J2") (pin "GND") (pinfunction "GND_GND") (pintype "bidirectional"))
      (node (ref "J2") (pin "GNDBREAK") (pinfunction "GNDBREAK_GNDBREAK") (pintype "bidirectional"))
      (node (ref "JP1") (pin "1") (pinfunction "1_1") (pintype "passive"))
      (node (ref "JP1") (pin "2") (pinfunction "2_2") (pintype "passive"))
      (node (ref "JP2") (pin "1") (pinfunction "1_1") (pintype "passive"))
      (node (ref "JP3") (pin "30") (pinfunction "30_30") (pintype "passive"))
      (node (ref "Q1") (pin "1") (pinfunction "E_1") (pintype "passive"))
      (node (ref "QG1") (pin "7") (pinfunction "GND_7") (pintype "power_in"))
      (node (ref "R20") (pin "P$1") (pinfunction "1_P$1") (pintype "passive"))
      (node (ref "R21") (pin "P$2") (pinfunction "2_P$2") (pintype "passive"))
      (node (ref "R25") (pin "P$2") (pinfunction "2_P$2") (pintype "passive"))
      (node (ref "RESET") (pin "1") (pinfunction "1_1") (pintype "passive"))
      (node (ref "X1") (pin "3") (pinfunction "3_3") (pintype "passive"))
      (node (ref "X1") (pin "SH1") (pinfunction "PE1_SH1") (pintype "power_in"))
      (node (ref "X1") (pin "SH2") (pinfunction "PE2_SH2") (pintype "power_in"))
      (node (ref "X1") (pin "SH3") (pinfunction "PE3_SH3") (pintype "power_in"))
    )
    (net (code "65") (name "Net-(C2-+)") (class "Default")
      (node (ref "C2") (pin "1") (pinfunction "+_1") (pintype "passive"))
      (node (ref "IC10") (pin "1") (pinfunction "C1+_1") (pintype "bidirectional"))
    )
    (net (code "66") (name "Net-(C2--)") (class "Default")
      (node (ref "C2") (pin "2") (pinfunction "-_2") (pintype "passive"))
      (node (ref "IC10") (pin "3") (pinfunction "C1-_3") (pintype "bidirectional"))
    )
    (net (code "67") (name "Net-(C3-+)") (class "Default")
      (node (ref "C3") (pin "1") (pinfunction "+_1") (pintype "passive"))
      (node (ref "IC10") (pin "4") (pinfunction "C2+_4") (pintype "bidirectional"))
    )
    (net (code "68") (name "Net-(C3--)") (class "Default")
      (node (ref "C3") (pin "2") (pinfunction "-_2") (pintype "passive"))
      (node (ref "IC10") (pin "5") (pinfunction "C2-_5") (pintype "bidirectional"))
    )
    (net (code "69") (name "Net-(C4-Pad1)") (class "Default")
      (node (ref "C4") (pin "1") (pinfunction "1_1") (pintype "passive"))
      (node (ref "CON1") (pin "4") (pinfunction "4_4") (pintype "passive"))
    )
    (net (code "70") (name "Net-(C5-+)") (class "Default")
      (node (ref "C5") (pin "1") (pinfunction "+_1") (pintype "passive"))
      (node (ref "IC10") (pin "2") (pinfunction "V+_2") (pintype "bidirectional"))
    )
    (net (code "71") (name "Net-(C6-+)") (class "Default")
      (node (ref "C6") (pin "1") (pinfunction "+_1") (pintype "passive"))
      (node (ref "IC10") (pin "6") (pinfunction "V-_6") (pintype "bidirectional"))
    )
    (net (code "72") (name "Net-(CON1-Pad1)") (class "Default")
      (node (ref "CON1") (pin "1") (pinfunction "1_1") (pintype "passive"))
      (node (ref "CON1") (pin "6") (pinfunction "6_6") (pintype "passive"))
    )
    (net (code "73") (name "Net-(IC2-~{WE})") (class "Default")
      (node (ref "IC2") (pin "27") (pinfunction "~{WE}_27") (pintype "input"))
      (node (ref "IC4") (pin "11") (pinfunction "O_11") (pintype "output"))
    )
    (net (code "74") (name "Net-(IC3-~{CE})") (class "Default")
      (node (ref "IC3") (pin "20") (pinfunction "~{CE}_20") (pintype "input"))
      (node (ref "IC3") (pin "22") (pinfunction "~{OE}_22") (pintype "input"))
      (node (ref "IC4") (pin "8") (pinfunction "O_8") (pintype "output"))
    )
    (net (code "75") (name "Net-(IC4A-I0)") (class "Default")
      (node (ref "IC4") (pin "1") (pinfunction "I0_1") (pintype "input"))
      (node (ref "IC5") (pin "9") (pinfunction "Y6_9") (pintype "output"))
    )
    (net (code "76") (name "Net-(IC4A-I1)") (class "Default")
      (node (ref "IC4") (pin "2") (pinfunction "I1_2") (pintype "input"))
      (node (ref "IC5") (pin "7") (pinfunction "Y7_7") (pintype "output"))
    )
    (net (code "77") (name "Net-(IC4A-O)") (class "Default")
      (node (ref "IC4") (pin "10") (pinfunction "I1_10") (pintype "input"))
      (node (ref "IC4") (pin "3") (pinfunction "O_3") (pintype "output"))
      (node (ref "IC4") (pin "9") (pinfunction "I0_9") (pintype "input"))
    )
    (net (code "78") (name "Net-(IC4B-O)") (class "Default")
      (node (ref "IC4") (pin "13") (pinfunction "I1_13") (pintype "input"))
      (node (ref "IC4") (pin "6") (pinfunction "O_6") (pintype "output"))
    )
    (net (code "79") (name "Net-(IC6A-CB2)") (class "Default")
      (node (ref "C1") (pin "1") (pinfunction "1_1") (pintype "passive"))
      (node (ref "IC6") (pin "19") (pinfunction "CB2_19") (pintype "bidirectional"))
      (node (ref "IC7") (pin "3") (pinfunction "I_3") (pintype "input"))
    )
    (net (code "80") (name "Net-(IC8-P0)") (class "Default")
      (node (ref "IC8") (pin "1") (pinfunction "P0_1") (pintype "bidirectional"))
      (node (ref "R5") (pin "P$1") (pinfunction "1_P$1") (pintype "passive"))
    )
    (net (code "81") (name "Net-(IC8-P1)") (class "Default")
      (node (ref "IC8") (pin "2") (pinfunction "P1_2") (pintype "bidirectional"))
      (node (ref "R6") (pin "P$1") (pinfunction "1_P$1") (pintype "passive"))
    )
    (net (code "82") (name "Net-(IC8-P2)") (class "Default")
      (node (ref "IC8") (pin "3") (pinfunction "P2_3") (pintype "bidirectional"))
      (node (ref "R7") (pin "P$1") (pinfunction "1_P$1") (pintype "passive"))
    )
    (net (code "83") (name "Net-(IC8-P3)") (class "Default")
      (node (ref "IC8") (pin "4") (pinfunction "P3_4") (pintype "bidirectional"))
      (node (ref "R8") (pin "P$1") (pinfunction "1_P$1") (pintype "passive"))
    )
    (net (code "84") (name "Net-(IC8-P4)") (class "Default")
      (node (ref "IC8") (pin "5") (pinfunction "P4_5") (pintype "bidirectional"))
      (node (ref "R9") (pin "P$1") (pinfunction "1_P$1") (pintype "passive"))
    )
    (net (code "85") (name "Net-(IC8-P5)") (class "Default")
      (node (ref "IC8") (pin "6") (pinfunction "P5_6") (pintype "bidirectional"))
      (node (ref "R10") (pin "P$1") (pinfunction "1_P$1") (pintype "passive"))
    )
    (net (code "86") (name "Net-(IC8-P6)") (class "Default")
      (node (ref "IC8") (pin "7") (pinfunction "P6_7") (pintype "bidirectional"))
      (node (ref "R11") (pin "P$1") (pinfunction "1_P$1") (pintype "passive"))
    )
    (net (code "87") (name "Net-(IC8-P7)") (class "Default")
      (node (ref "IC8") (pin "8") (pinfunction "P7_8") (pintype "bidirectional"))
      (node (ref "R12") (pin "P$1") (pinfunction "1_P$1") (pintype "passive"))
    )
    (net (code "88") (name "Net-(IC8-P12)") (class "Default")
      (node (ref "IC8") (pin "17") (pinfunction "P12_17") (pintype "bidirectional"))
      (node (ref "R14") (pin "P$1") (pinfunction "1_P$1") (pintype "passive"))
    )
    (net (code "89") (name "Net-(IC8-P13)") (class "Default")
      (node (ref "IC8") (pin "18") (pinfunction "P13_18") (pintype "bidirectional"))
      (node (ref "R15") (pin "P$1") (pinfunction "1_P$1") (pintype "passive"))
    )
    (net (code "90") (name "Net-(IC8-P14)") (class "Default")
      (node (ref "IC8") (pin "19") (pinfunction "P14_19") (pintype "bidirectional"))
      (node (ref "R16") (pin "P$1") (pinfunction "1_P$1") (pintype "passive"))
    )
    (net (code "91") (name "Net-(IC8-P28)") (class "Default")
      (node (ref "IC8") (pin "37") (pinfunction "P28_37") (pintype "bidirectional"))
      (node (ref "IC9") (pin "6") (pinfunction "SCL_6") (pintype "input"))
    )
    (net (code "92") (name "Net-(IC8-P29)") (class "Default")
      (node (ref "IC8") (pin "38") (pinfunction "P29_38") (pintype "bidirectional"))
      (node (ref "IC9") (pin "5") (pinfunction "SDA_5") (pintype "bidirectional"))
      (node (ref "R17") (pin "P$1") (pinfunction "1_P$1") (pintype "passive"))
    )
    (net (code "93") (name "Net-(IC8-XI)") (class "Default")
      (node (ref "IC8") (pin "30") (pinfunction "XI_30") (pintype "input"))
      (node (ref "Y1") (pin "2") (pinfunction "2_2") (pintype "passive"))
    )
    (net (code "94") (name "Net-(IC8-XO)") (class "Default")
      (node (ref "IC8") (pin "31") (pinfunction "XO_31") (pintype "output"))
      (node (ref "Y1") (pin "1") (pinfunction "1_1") (pintype "passive"))
    )
    (net (code "95") (name "Net-(IC10A-R1IN)") (class "Default")
      (node (ref "CON1") (pin "3") (pinfunction "3_3") (pintype "passive"))
      (node (ref "IC10") (pin "13") (pinfunction "R1IN_13") (pintype "input"))
    )
    (net (code "96") (name "Net-(IC10A-R1OUT)") (class "Default")
      (node (ref "IC10") (pin "12") (pinfunction "R1OUT_12") (pintype "output"))
      (node (ref "R18") (pin "P$2") (pinfunction "2_P$2") (pintype "passive"))
    )
    (net (code "97") (name "Net-(IC10A-T1OUT)") (class "Default")
      (node (ref "CON1") (pin "2") (pinfunction "2_2") (pintype "passive"))
      (node (ref "IC10") (pin "14") (pinfunction "T1OUT_14") (pintype "output"))
    )
    (net (code "98") (name "Net-(LED1-C)") (class "Default")
      (node (ref "LED1") (pin "K") (pinfunction "C_K") (pintype "passive"))
      (node (ref "R25") (pin "P$1") (pinfunction "1_P$1") (pintype "passive"))
    )
    (net (code "99") (name "Net-(Q1-B)") (class "Default")
      (node (ref "Q1") (pin "2") (pinfunction "B_2") (pintype "passive"))
      (node (ref "R19") (pin "P$2") (pinfunction "2_P$2") (pintype "passive"))
      (node (ref "R20") (pin "P$2") (pinfunction "2_P$2") (pintype "passive"))
    )
    (net (code "100") (name "Net-(R14-2)") (class "Default")
      (node (ref "J1") (pin "PIN") (pinfunction "PIN_PIN") (pintype "bidirectional"))
      (node (ref "R14") (pin "P$2") (pinfunction "2_P$2") (pintype "passive"))
      (node (ref "R15") (pin "P$2") (pinfunction "2_P$2") (pintype "passive"))
      (node (ref "R16") (pin "P$2") (pinfunction "2_P$2") (pintype "passive"))
    )
    (net (code "101") (name "Net-(R19-1)") (class "Default")
      (node (ref "C4") (pin "2") (pinfunction "2_2") (pintype "passive"))
      (node (ref "R19") (pin "P$1") (pinfunction "1_P$1") (pintype "passive"))
    )
    (net (code "102") (name "Net-(R26-1)") (class "Default")
      (node (ref "R26") (pin "P$1") (pinfunction "1_P$1") (pintype "passive"))
      (node (ref "R27") (pin "P$2") (pinfunction "2_P$2") (pintype "passive"))
      (node (ref "X1") (pin "6") (pinfunction "6_6") (pintype "passive"))
    )
    (net (code "103") (name "Net-(R28-1)") (class "Default")
      (node (ref "R28") (pin "P$1") (pinfunction "1_P$1") (pintype "passive"))
      (node (ref "R29") (pin "P$2") (pinfunction "2_P$2") (pintype "passive"))
      (node (ref "X1") (pin "1") (pinfunction "1_1") (pintype "passive"))
    )
    (net (code "104") (name "VCC") (class "Default")
      (node (ref "C1") (pin "2") (pinfunction "2_2") (pintype "passive"))
      (node (ref "C11") (pin "1") (pinfunction "1_1") (pintype "passive"))
      (node (ref "C12") (pin "1") (pinfunction "1_1") (pintype "passive"))
      (node (ref "C13") (pin "1") (pinfunction "1_1") (pintype "passive"))
      (node (ref "C14") (pin "1") (pinfunction "1_1") (pintype "passive"))
      (node (ref "C15") (pin "1") (pinfunction "1_1") (pintype "passive"))
      (node (ref "C16") (pin "1") (pinfunction "1_1") (pintype "passive"))
      (node (ref "C17") (pin "1") (pinfunction "1_1") (pintype "passive"))
      (node (ref "C18") (pin "1") (pinfunction "1_1") (pintype "passive"))
      (node (ref "C19") (pin "1") (pinfunction "1_1") (pintype "passive"))
      (node (ref "C5") (pin "2") (pinfunction "-_2") (pintype "passive"))
      (node (ref "C7") (pin "1") (pinfunction "+_1") (pintype "passive"))
      (node (ref "C8") (pin "1") (pinfunction "+_1") (pintype "passive"))
      (node (ref "C9") (pin "1") (pinfunction "+_1") (pintype "passive"))
      (node (ref "IC1") (pin "8") (pinfunction "VDD_8") (pintype "power_in"))
      (node (ref "IC10") (pin "16") (pinfunction "VCC_16") (pintype "power_in"))
      (node (ref "IC13") (pin "3") (pinfunction "IN_3") (pintype "input"))
      (node (ref "IC2") (pin "28") (pinfunction "VCC_28") (pintype "power_in"))
      (node (ref "IC3") (pin "27") (pinfunction "PGM_27") (pintype "input"))
      (node (ref "IC3") (pin "28") (pinfunction "VCC_28") (pintype "power_in"))
      (node (ref "IC4") (pin "14") (pinfunction "VCC_14") (pintype "power_in"))
      (node (ref "IC5") (pin "16") (pinfunction "VCC_16") (pintype "power_in"))
      (node (ref "IC6") (pin "20") (pinfunction "VCC_20") (pintype "power_in"))
      (node (ref "IC6") (pin "24") (pinfunction "CS1_24") (pintype "input"))
      (node (ref "IC6") (pin "9") (pinfunction "PA7_9") (pintype "bidirectional"))
      (node (ref "JP1") (pin "3") (pinfunction "3_3") (pintype "passive"))
      (node (ref "JP1") (pin "5") (pinfunction "5_5") (pintype "passive"))
      (node (ref "JP3") (pin "29") (pinfunction "29_29") (pintype "passive"))
      (node (ref "LED1") (pin "A") (pinfunction "A_A") (pintype "passive"))
      (node (ref "QG1") (pin "14") (pinfunction "VCC_14") (pintype "power_in"))
      (node (ref "R1") (pin "P$2") (pinfunction "2_P$2") (pintype "passive"))
      (node (ref "R2") (pin "P$2") (pinfunction "2_P$2") (pintype "passive"))
      (node (ref "R3") (pin "P$1") (pinfunction "1_P$1") (pintype "passive"))
      (node (ref "R4") (pin "P$2") (pinfunction "2_P$2") (pintype "passive"))
      (node (ref "S3") (pin "2") (pinfunction "2_2") (pintype "bidirectional"))
      (node (ref "X1") (pin "5") (pinfunction "5_5") (pintype "passive"))
    )
    (net (code "105") (name "unconnected-(CON1-Pad7)") (class "Default")
      (node (ref "CON1") (pin "7") (pinfunction "7_7") (pintype "passive"))
    )
    (net (code "106") (name "unconnected-(CON1-Pad8)") (class "Default")
      (node (ref "CON1") (pin "8") (pinfunction "8_8") (pintype "passive"))
    )
    (net (code "107") (name "unconnected-(CON1-Pad9)") (class "Default")
      (node (ref "CON1") (pin "9") (pinfunction "9_9") (pintype "passive"))
    )
    (net (code "108") (name "unconnected-(IC1A-BE-Pad36)") (class "Default")
      (node (ref "IC1") (pin "36") (pinfunction "BE_36") (pintype "input"))
    )
    (net (code "109") (name "unconnected-(IC1A-NC-Pad35)") (class "Default")
      (node (ref "IC1") (pin "35") (pinfunction "NC_35") (pintype "no_connect"))
    )
    (net (code "110") (name "unconnected-(IC1A-~{MLB}-Pad5)") (class "Default")
      (node (ref "IC1") (pin "5") (pinfunction "~{MLB}_5") (pintype "output"))
    )
    (net (code "111") (name "unconnected-(IC3-NC-Pad26)") (class "Default")
      (node (ref "IC3") (pin "26") (pinfunction "NC_26") (pintype "no_connect"))
    )
    (net (code "112") (name "unconnected-(IC3-VPP-Pad1)") (class "Default")
      (node (ref "IC3") (pin "1") (pinfunction "VPP_1") (pintype "input"))
    )
    (net (code "113") (name "unconnected-(IC5A-Y0-Pad15)") (class "Default")
      (node (ref "IC5") (pin "15") (pinfunction "Y0_15") (pintype "output"))
    )
    (net (code "114") (name "unconnected-(IC5A-Y1-Pad14)") (class "Default")
      (node (ref "IC5") (pin "14") (pinfunction "Y1_14") (pintype "output"))
    )
    (net (code "115") (name "unconnected-(IC6A-CA2-Pad39)") (class "Default")
      (node (ref "IC6") (pin "39") (pinfunction "CA2_39") (pintype "bidirectional"))
    )
    (net (code "116") (name "unconnected-(IC6A-IRQA-Pad38)") (class "Default")
      (node (ref "IC6") (pin "38") (pinfunction "IRQA_38") (pintype "open_collector"))
    )
    (net (code "117") (name "unconnected-(IC6A-IRQB-Pad37)") (class "Default")
      (node (ref "IC6") (pin "37") (pinfunction "IRQB_37") (pintype "open_collector"))
    )
    (net (code "118") (name "unconnected-(IC7A-I-Pad1)") (class "Default")
      (node (ref "IC7") (pin "1") (pinfunction "I_1") (pintype "input"))
    )
    (net (code "119") (name "unconnected-(IC7A-O-Pad2)") (class "Default")
      (node (ref "IC7") (pin "2") (pinfunction "O_2") (pintype "output"))
    )
    (net (code "120") (name "unconnected-(IC7C-I-Pad5)") (class "Default")
      (node (ref "IC7") (pin "5") (pinfunction "I_5") (pintype "input"))
    )
    (net (code "121") (name "unconnected-(IC7C-O-Pad6)") (class "Default")
      (node (ref "IC7") (pin "6") (pinfunction "O_6") (pintype "output"))
    )
    (net (code "122") (name "unconnected-(IC7D-I-Pad9)") (class "Default")
      (node (ref "IC7") (pin "9") (pinfunction "I_9") (pintype "input"))
    )
    (net (code "123") (name "unconnected-(IC7D-O-Pad8)") (class "Default")
      (node (ref "IC7") (pin "8") (pinfunction "O_8") (pintype "output"))
    )
    (net (code "124") (name "unconnected-(IC7E-I-Pad11)") (class "Default")
      (node (ref "IC7") (pin "11") (pinfunction "I_11") (pintype "input"))
    )
    (net (code "125") (name "unconnected-(IC7E-O-Pad10)") (class "Default")
      (node (ref "IC7") (pin "10") (pinfunction "O_10") (pintype "output"))
    )
    (net (code "126") (name "unconnected-(IC7F-I-Pad13)") (class "Default")
      (node (ref "IC7") (pin "13") (pinfunction "I_13") (pintype "input"))
    )
    (net (code "127") (name "unconnected-(IC7F-O-Pad12)") (class "Default")
      (node (ref "IC7") (pin "12") (pinfunction "O_12") (pintype "output"))
    )
    (net (code "128") (name "unconnected-(IC8-P9-Pad14)") (class "Default")
      (node (ref "IC8") (pin "14") (pinfunction "P9_14") (pintype "bidirectional"))
    )
    (net (code "129") (name "unconnected-(IC8-P10-Pad15)") (class "Default")
      (node (ref "IC8") (pin "15") (pinfunction "P10_15") (pintype "bidirectional"))
    )
    (net (code "130") (name "unconnected-(IC8-P11-Pad16)") (class "Default")
      (node (ref "IC8") (pin "16") (pinfunction "P11_16") (pintype "bidirectional"))
    )
    (net (code "131") (name "unconnected-(IC8-P15-Pad20)") (class "Default")
      (node (ref "IC8") (pin "20") (pinfunction "P15_20") (pintype "bidirectional"))
    )
    (net (code "132") (name "unconnected-(IC8-P24-Pad33)") (class "Default")
      (node (ref "IC8") (pin "33") (pinfunction "P24_33") (pintype "bidirectional"))
    )
    (net (code "133") (name "unconnected-(IC10A-R2IN-Pad8)") (class "Default")
      (node (ref "IC10") (pin "8") (pinfunction "R2IN_8") (pintype "input"))
    )
    (net (code "134") (name "unconnected-(IC10A-R2OUT-Pad9)") (class "Default")
      (node (ref "IC10") (pin "9") (pinfunction "R2OUT_9") (pintype "output"))
    )
    (net (code "135") (name "unconnected-(IC10A-T2IN-Pad10)") (class "Default")
      (node (ref "IC10") (pin "10") (pinfunction "T2IN_10") (pintype "input"))
    )
    (net (code "136") (name "unconnected-(IC10A-T2OUT-Pad7)") (class "Default")
      (node (ref "IC10") (pin "7") (pinfunction "T2OUT_7") (pintype "output"))
    )
    (net (code "137") (name "unconnected-(J1-PadSWITCH)") (class "Default")
      (node (ref "J1") (pin "SWITCH") (pinfunction "SWITCH_SWITCH") (pintype "bidirectional"))
    )
    (net (code "138") (name "unconnected-(S3-C_2-Pad6)") (class "Default")
      (node (ref "S3") (pin "6") (pinfunction "C_2_6") (pintype "bidirectional"))
    )
    (net (code "139") (name "unconnected-(S3-Pad3)") (class "Default")
      (node (ref "S3") (pin "3") (pinfunction "3_3") (pintype "bidirectional"))
    )
    (net (code "140") (name "unconnected-(S3-Pad4)") (class "Default")
      (node (ref "S3") (pin "4") (pinfunction "4_4") (pintype "bidirectional"))
    )
    (net (code "141") (name "unconnected-(S3-Pad5)") (class "Default")
      (node (ref "S3") (pin "5") (pinfunction "5_5") (pintype "bidirectional"))
    )
    (net (code "142") (name "unconnected-(X1-Pad2)") (class "Default")
      (node (ref "X1") (pin "2") (pinfunction "2_2") (pintype "passive"))
    )
    (net (code "143") (name "unconnected-(X1-Pad8)") (class "Default")
      (node (ref "X1") (pin "8") (pinfunction "8_8") (pintype "passive"))
    )
  )
)
